# MySensors_AirQuality_Board_2017-11-21_i2.net
KiCad netlist of a schematic drawn in EAGLE
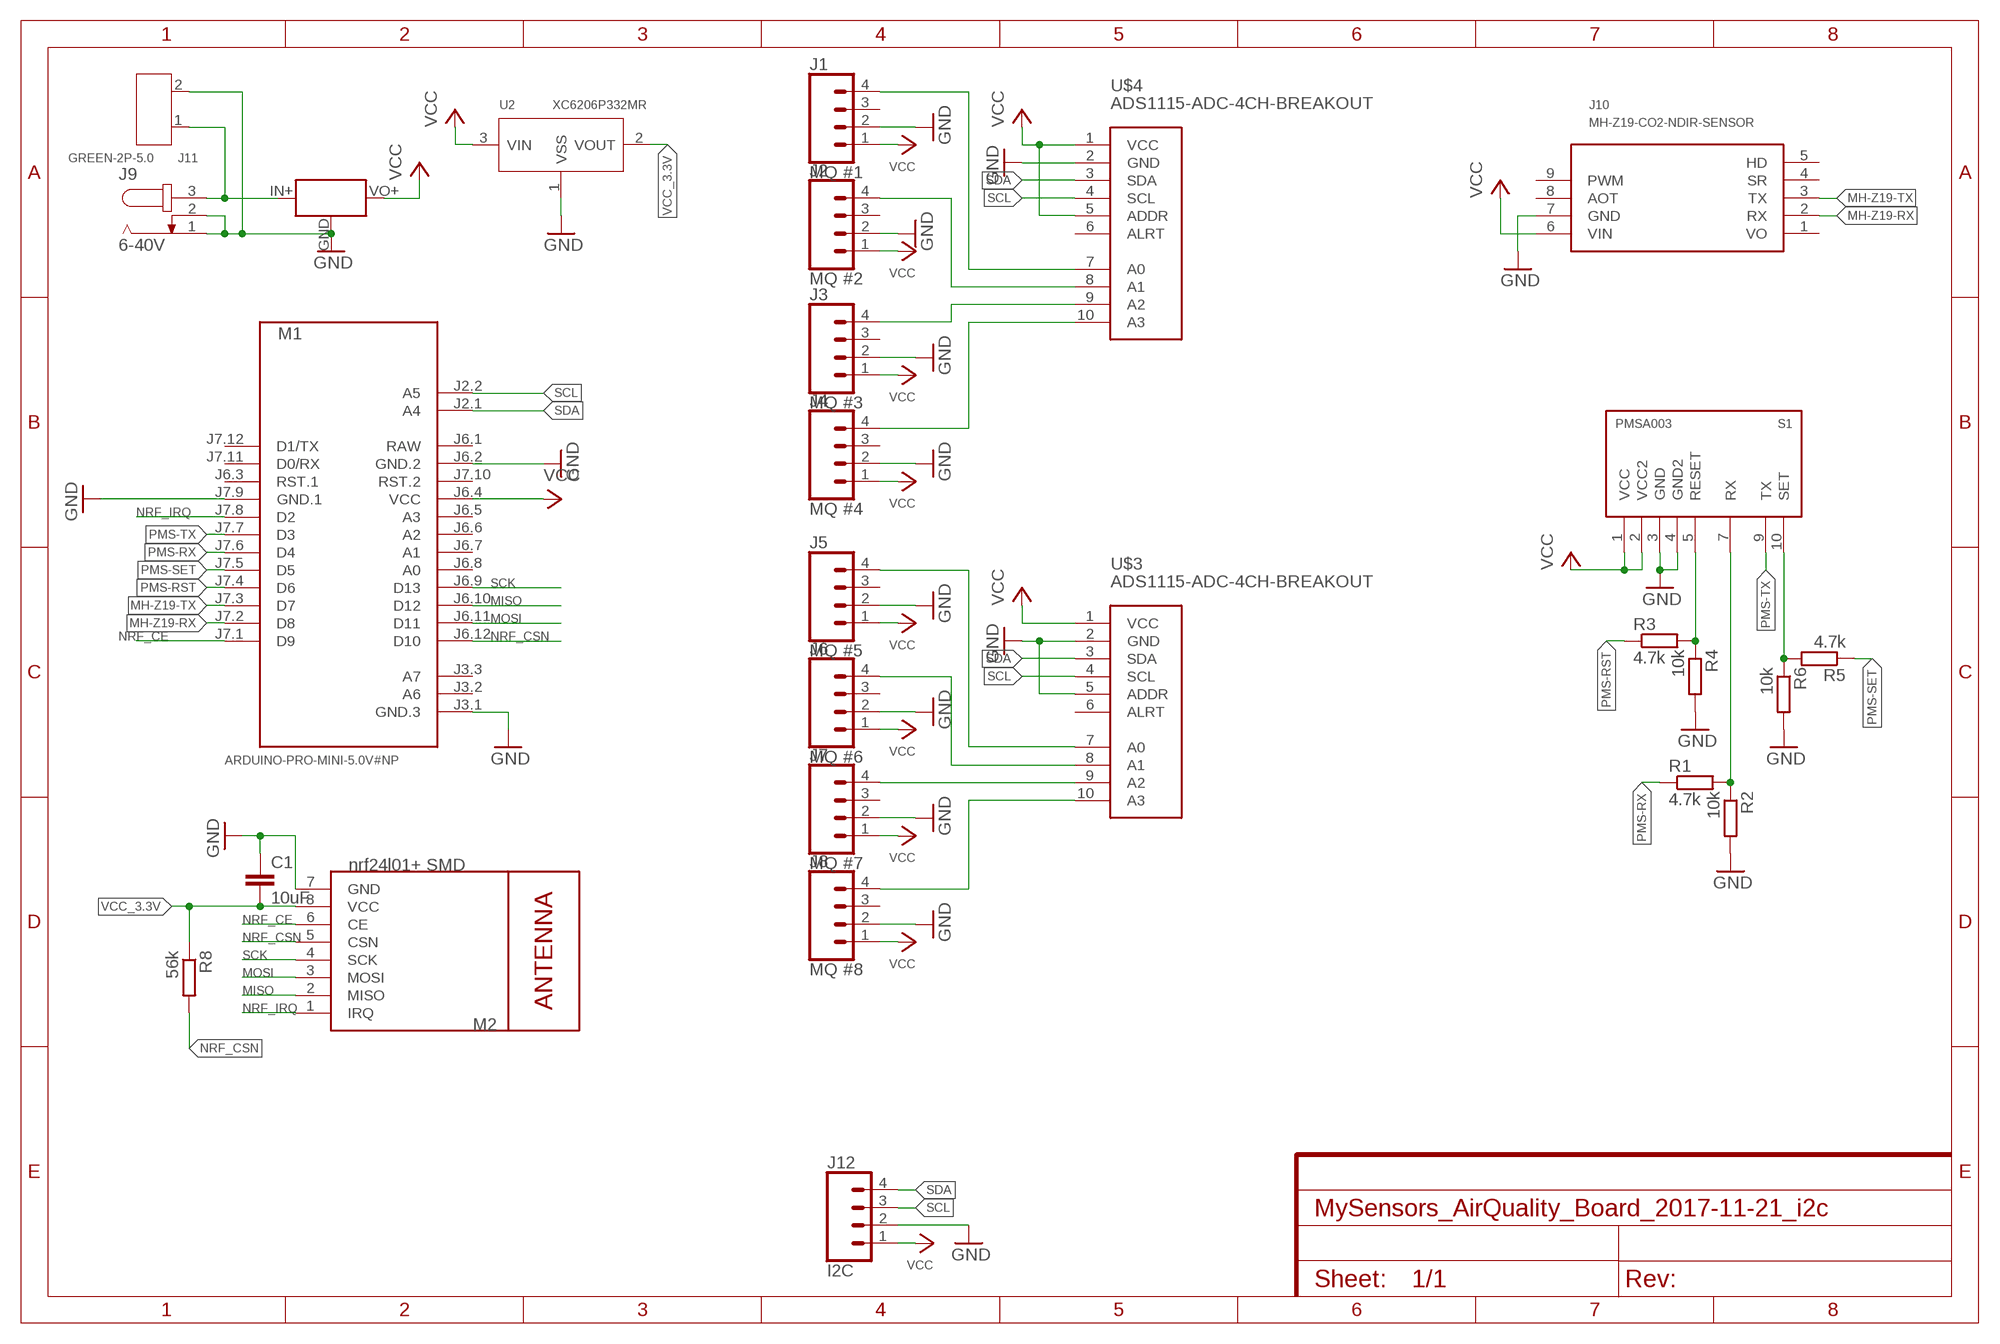
[diagram p0: schematic, sheet 1]

(export (version "E")
  (design (tool "Eeschema 10.0.6"))
  (components
    (comp (ref "C1")
      (value "10uF")
      (footprint "eagle-import:C0805")
      (libsource (lib "eagle-import") (part "C-EUC0805"))
    )
    (comp (ref "J1")
      (value "MQ #1")
      (footprint "eagle-import:1X04")
      (libsource (lib "eagle-import") (part "CONN_04"))
    )
    (comp (ref "J2")
      (value "MQ #2")
      (footprint "eagle-import:1X04")
      (libsource (lib "eagle-import") (part "CONN_04"))
    )
    (comp (ref "J3")
      (value "MQ #3")
      (footprint "eagle-import:1X04")
      (libsource (lib "eagle-import") (part "CONN_04"))
    )
    (comp (ref "J4")
      (value "MQ #4")
      (footprint "eagle-import:1X04")
      (libsource (lib "eagle-import") (part "CONN_04"))
    )
    (comp (ref "J5")
      (value "MQ #5")
      (footprint "eagle-import:1X04")
      (libsource (lib "eagle-import") (part "CONN_04"))
    )
    (comp (ref "J6")
      (value "MQ #6")
      (footprint "eagle-import:1X04")
      (libsource (lib "eagle-import") (part "CONN_04"))
    )
    (comp (ref "J7")
      (value "MQ #7")
      (footprint "eagle-import:1X04")
      (libsource (lib "eagle-import") (part "CONN_04"))
    )
    (comp (ref "J8")
      (value "MQ #8")
      (footprint "eagle-import:1X04")
      (libsource (lib "eagle-import") (part "CONN_04"))
    )
    (comp (ref "J9")
      (value "6-40V")
      (footprint "eagle-import:SPC4078")
      (libsource (lib "eagle-import") (part "JACK-PLUG1"))
    )
    (comp (ref "J10")
      (value "MH-Z19-CO2-NDIR-SENSOR")
      (footprint "eagle-import:MH-Z19")
      (libsource (lib "eagle-import") (part "MH-Z19-CO2-NDIR-SENSOR"))
    )
    (comp (ref "J11")
      (value "GREEN-2P-5.0")
      (footprint "eagle-import:H2-5.0-10.5X8.0MM")
      (libsource (lib "eagle-import") (part "SCREW-TERMINAL-GREEN(2P-5.0)"))
    )
    (comp (ref "J12")
      (value "I2C")
      (footprint "eagle-import:1X04")
      (libsource (lib "eagle-import") (part "CONN_04"))
    )
    (comp (ref "M1")
      (value "ARDUINO-PRO-MINI-5.0V#NP")
      (footprint "eagle-import:ARDUINO-PRO-MINI#NP")
      (libsource (lib "eagle-import") (part "ARDUINO-PRO-MINI-#NP5.0V"))
    )
    (comp (ref "M2")
      (value "nrf24l01+ SMD")
      (footprint "eagle-import:WIRELESS-NRF24L01-SMD")
      (libsource (lib "eagle-import") (part "WIRELESS-NRF24L01SMD"))
    )
    (comp (ref "R1")
      (value "4.7k")
      (footprint "eagle-import:R0805")
      (libsource (lib "eagle-import") (part "resistor_348_R-EU_R0805"))
    )
    (comp (ref "R2")
      (value "10k")
      (footprint "eagle-import:R0805")
      (libsource (lib "eagle-import") (part "resistor_348_R-EU_R0805"))
    )
    (comp (ref "R3")
      (value "4.7k")
      (footprint "eagle-import:R0805")
      (libsource (lib "eagle-import") (part "resistor_348_R-EU_R0805"))
    )
    (comp (ref "R4")
      (value "10k")
      (footprint "eagle-import:R0805")
      (libsource (lib "eagle-import") (part "resistor_348_R-EU_R0805"))
    )
    (comp (ref "R5")
      (value "4.7k")
      (footprint "eagle-import:R0805")
      (libsource (lib "eagle-import") (part "resistor_348_R-EU_R0805"))
    )
    (comp (ref "R6")
      (value "10k")
      (footprint "eagle-import:R0805")
      (libsource (lib "eagle-import") (part "resistor_348_R-EU_R0805"))
    )
    (comp (ref "R8")
      (value "56k")
      (footprint "eagle-import:R0805")
      (libsource (lib "eagle-import") (part "R-EU_R0805"))
    )
    (comp (ref "S1")
      (value "PMSA003")
      (footprint "eagle-import:PMSA003")
      (libsource (lib "eagle-import") (part "PMSA003"))
    )
    (comp (ref "U$2")
      (value "MINI_BUCK_CONVERTER")
      (footprint "eagle-import:MINI_BUCK_CONVERTER")
      (libsource (lib "eagle-import") (part "MINI_BUCK_CONVERTER"))
    )
    (comp (ref "U$3")
      (value "ADS1115-ADC-4CH-BREAKOUT")
      (footprint "eagle-import:ADS1115-ADC-4CH-BREAKOUT")
      (libsource (lib "eagle-import") (part "ADS1115-ADC-4CH-BREAKOUT"))
    )
    (comp (ref "U$4")
      (value "ADS1115-ADC-4CH-BREAKOUT")
      (footprint "eagle-import:ADS1115-ADC-4CH-BREAKOUT")
      (libsource (lib "eagle-import") (part "ADS1115-ADC-4CH-BREAKOUT"))
    )
    (comp (ref "U2")
      (value "XC6206P332MR")
      (footprint "eagle-import:SOT-23")
      (fields (field (name "MPN") "XC6206P332MR-G"))
      (libsource (lib "eagle-import") (part "PMIC-LDO-XC6206P332MR-G(SOT23)"))
    )
  )
  (nets
    (net (code "1") (name "/MISO") (class "Default")
      (node (ref "M1") (pin "J6.10") (pinfunction "D12_J6.10") (pintype "bidirectional"))
      (node (ref "M2") (pin "2") (pinfunction "MISO_2") (pintype "bidirectional"))
    )
    (net (code "2") (name "/MOSI") (class "Default")
      (node (ref "M1") (pin "J6.11") (pinfunction "D11_J6.11") (pintype "bidirectional"))
      (node (ref "M2") (pin "3") (pinfunction "MOSI_3") (pintype "bidirectional"))
    )
    (net (code "3") (name "/NRF_CE") (class "Default")
      (node (ref "M1") (pin "J7.1") (pinfunction "D9_J7.1") (pintype "bidirectional"))
      (node (ref "M2") (pin "6") (pinfunction "CE_6") (pintype "bidirectional"))
    )
    (net (code "4") (name "/NRF_IRQ") (class "Default")
      (node (ref "M1") (pin "J7.8") (pinfunction "D2_J7.8") (pintype "bidirectional"))
      (node (ref "M2") (pin "1") (pinfunction "IRQ_1") (pintype "bidirectional"))
    )
    (net (code "5") (name "/RAW") (class "Default")
      (node (ref "M1") (pin "J6.1") (pinfunction "RAW_J6.1") (pintype "power_in"))
    )
    (net (code "6") (name "/SCK") (class "Default")
      (node (ref "M1") (pin "J6.9") (pinfunction "D13_J6.9") (pintype "bidirectional"))
      (node (ref "M2") (pin "4") (pinfunction "SCK_4") (pintype "bidirectional"))
    )
    (net (code "7") (name "/VO") (class "Default")
      (node (ref "J10") (pin "1") (pinfunction "VO_1") (pintype "power_in"))
    )
    (net (code "8") (name "GND") (class "Default")
      (node (ref "C1") (pin "1") (pinfunction "1_1") (pintype "passive"))
      (node (ref "J1") (pin "2") (pinfunction "2_2") (pintype "passive"))
      (node (ref "J10") (pin "7") (pinfunction "GND_7") (pintype "power_in"))
      (node (ref "J11") (pin "2") (pinfunction "2_2") (pintype "bidirectional"))
      (node (ref "J12") (pin "2") (pinfunction "2_2") (pintype "passive"))
      (node (ref "J2") (pin "2") (pinfunction "2_2") (pintype "passive"))
      (node (ref "J3") (pin "2") (pinfunction "2_2") (pintype "passive"))
      (node (ref "J4") (pin "2") (pinfunction "2_2") (pintype "passive"))
      (node (ref "J5") (pin "2") (pinfunction "2_2") (pintype "passive"))
      (node (ref "J6") (pin "2") (pinfunction "2_2") (pintype "passive"))
      (node (ref "J7") (pin "2") (pinfunction "2_2") (pintype "passive"))
      (node (ref "J8") (pin "2") (pinfunction "2_2") (pintype "passive"))
      (node (ref "J9") (pin "1") (pinfunction "1_1") (pintype "passive"))
      (node (ref "J9") (pin "2") (pinfunction "2_2") (pintype "passive"))
      (node (ref "M1") (pin "J3.1") (pinfunction "GND.3_J3.1") (pintype "bidirectional"))
      (node (ref "M1") (pin "J6.2") (pinfunction "GND.2_J6.2") (pintype "power_in"))
      (node (ref "M1") (pin "J7.9") (pinfunction "GND.1_J7.9") (pintype "power_in"))
      (node (ref "M2") (pin "7") (pinfunction "GND_7") (pintype "power_in"))
      (node (ref "R2") (pin "2") (pinfunction "2_2") (pintype "passive"))
      (node (ref "R4") (pin "2") (pinfunction "2_2") (pintype "passive"))
      (node (ref "R6") (pin "2") (pinfunction "2_2") (pintype "passive"))
      (node (ref "S1") (pin "3") (pinfunction "GND_3") (pintype "bidirectional"))
      (node (ref "S1") (pin "4") (pinfunction "GND2_4") (pintype "bidirectional"))
      (node (ref "U$2") (pin "GND") (pinfunction "GND_GND") (pintype "bidirectional"))
      (node (ref "U$3") (pin "2") (pinfunction "GND_2") (pintype "power_in"))
      (node (ref "U$3") (pin "5") (pinfunction "ADDR_5") (pintype "bidirectional"))
      (node (ref "U$4") (pin "2") (pinfunction "GND_2") (pintype "power_in"))
      (node (ref "U2") (pin "1") (pinfunction "VSS_1") (pintype "power_in"))
    )
    (net (code "9") (name "MH-Z19-RX") (class "Default")
      (node (ref "J10") (pin "2") (pinfunction "RX_2") (pintype "input"))
      (node (ref "M1") (pin "J7.2") (pinfunction "D8_J7.2") (pintype "bidirectional"))
    )
    (net (code "10") (name "MH-Z19-TX") (class "Default")
      (node (ref "J10") (pin "3") (pinfunction "TX_3") (pintype "output"))
      (node (ref "M1") (pin "J7.3") (pinfunction "D7_J7.3") (pintype "bidirectional"))
    )
    (net (code "11") (name "NRF_CSN") (class "Default")
      (node (ref "M1") (pin "J6.12") (pinfunction "D10_J6.12") (pintype "bidirectional"))
      (node (ref "M2") (pin "5") (pinfunction "CSN_5") (pintype "bidirectional"))
      (node (ref "R8") (pin "2") (pinfunction "2_2") (pintype "passive"))
    )
    (net (code "12") (name "Net-(S1-RESET)") (class "Default")
      (node (ref "R3") (pin "2") (pinfunction "2_2") (pintype "passive"))
      (node (ref "R4") (pin "1") (pinfunction "1_1") (pintype "passive"))
      (node (ref "S1") (pin "5") (pinfunction "RESET_5") (pintype "bidirectional"))
    )
    (net (code "13") (name "Net-(S1-RX)") (class "Default")
      (node (ref "R1") (pin "2") (pinfunction "2_2") (pintype "passive"))
      (node (ref "R2") (pin "1") (pinfunction "1_1") (pintype "passive"))
      (node (ref "S1") (pin "7") (pinfunction "RX_7") (pintype "bidirectional"))
    )
    (net (code "14") (name "Net-(S1-SET)") (class "Default")
      (node (ref "R5") (pin "2") (pinfunction "2_2") (pintype "passive"))
      (node (ref "R6") (pin "1") (pinfunction "1_1") (pintype "passive"))
      (node (ref "S1") (pin "10") (pinfunction "SET_10") (pintype "bidirectional"))
    )
    (net (code "15") (name "Net-(U$2-VIN)") (class "Default")
      (node (ref "J11") (pin "1") (pinfunction "1_1") (pintype "bidirectional"))
      (node (ref "J9") (pin "3") (pinfunction "3_3") (pintype "passive"))
      (node (ref "U$2") (pin "IN+") (pinfunction "VIN_IN+") (pintype "input"))
    )
    (net (code "16") (name "Net-(U$3-A0)") (class "Default")
      (node (ref "J5") (pin "4") (pinfunction "4_4") (pintype "passive"))
      (node (ref "U$3") (pin "7") (pinfunction "A0_7") (pintype "input"))
    )
    (net (code "17") (name "Net-(U$3-A1)") (class "Default")
      (node (ref "J6") (pin "4") (pinfunction "4_4") (pintype "passive"))
      (node (ref "U$3") (pin "8") (pinfunction "A1_8") (pintype "input"))
    )
    (net (code "18") (name "Net-(U$3-A2)") (class "Default")
      (node (ref "J7") (pin "4") (pinfunction "4_4") (pintype "passive"))
      (node (ref "U$3") (pin "9") (pinfunction "A2_9") (pintype "input"))
    )
    (net (code "19") (name "Net-(U$3-A3)") (class "Default")
      (node (ref "J8") (pin "4") (pinfunction "4_4") (pintype "passive"))
      (node (ref "U$3") (pin "10") (pinfunction "A3_10") (pintype "input"))
    )
    (net (code "20") (name "Net-(U$4-A0)") (class "Default")
      (node (ref "J1") (pin "4") (pinfunction "4_4") (pintype "passive"))
      (node (ref "U$4") (pin "7") (pinfunction "A0_7") (pintype "input"))
    )
    (net (code "21") (name "Net-(U$4-A1)") (class "Default")
      (node (ref "J2") (pin "4") (pinfunction "4_4") (pintype "passive"))
      (node (ref "U$4") (pin "8") (pinfunction "A1_8") (pintype "input"))
    )
    (net (code "22") (name "Net-(U$4-A2)") (class "Default")
      (node (ref "J3") (pin "4") (pinfunction "4_4") (pintype "passive"))
      (node (ref "U$4") (pin "9") (pinfunction "A2_9") (pintype "input"))
    )
    (net (code "23") (name "Net-(U$4-A3)") (class "Default")
      (node (ref "J4") (pin "4") (pinfunction "4_4") (pintype "passive"))
      (node (ref "U$4") (pin "10") (pinfunction "A3_10") (pintype "input"))
    )
    (net (code "24") (name "PMS-RST") (class "Default")
      (node (ref "M1") (pin "J7.4") (pinfunction "D6_J7.4") (pintype "bidirectional"))
      (node (ref "R3") (pin "1") (pinfunction "1_1") (pintype "passive"))
    )
    (net (code "25") (name "PMS-RX") (class "Default")
      (node (ref "M1") (pin "J7.6") (pinfunction "D4_J7.6") (pintype "bidirectional"))
      (node (ref "R1") (pin "1") (pinfunction "1_1") (pintype "passive"))
    )
    (net (code "26") (name "PMS-SET") (class "Default")
      (node (ref "M1") (pin "J7.5") (pinfunction "D5_J7.5") (pintype "bidirectional"))
      (node (ref "R5") (pin "1") (pinfunction "1_1") (pintype "passive"))
    )
    (net (code "27") (name "PMS-TX") (class "Default")
      (node (ref "M1") (pin "J7.7") (pinfunction "D3_J7.7") (pintype "bidirectional"))
      (node (ref "S1") (pin "9") (pinfunction "TX_9") (pintype "bidirectional"))
    )
    (net (code "28") (name "SCL") (class "Default")
      (node (ref "J12") (pin "3") (pinfunction "3_3") (pintype "passive"))
      (node (ref "M1") (pin "J2.2") (pinfunction "A5_J2.2") (pintype "bidirectional"))
      (node (ref "U$3") (pin "4") (pinfunction "SCL_4") (pintype "bidirectional"))
      (node (ref "U$4") (pin "4") (pinfunction "SCL_4") (pintype "bidirectional"))
    )
    (net (code "29") (name "SDA") (class "Default")
      (node (ref "J12") (pin "4") (pinfunction "4_4") (pintype "passive"))
      (node (ref "M1") (pin "J2.1") (pinfunction "A4_J2.1") (pintype "bidirectional"))
      (node (ref "U$3") (pin "3") (pinfunction "SDA_3") (pintype "bidirectional"))
      (node (ref "U$4") (pin "3") (pinfunction "SDA_3") (pintype "bidirectional"))
    )
    (net (code "30") (name "VCC") (class "Default")
      (node (ref "J1") (pin "1") (pinfunction "1_1") (pintype "passive"))
      (node (ref "J10") (pin "6") (pinfunction "VIN_6") (pintype "power_in"))
      (node (ref "J12") (pin "1") (pinfunction "1_1") (pintype "passive"))
      (node (ref "J2") (pin "1") (pinfunction "1_1") (pintype "passive"))
      (node (ref "J3") (pin "1") (pinfunction "1_1") (pintype "passive"))
      (node (ref "J4") (pin "1") (pinfunction "1_1") (pintype "passive"))
      (node (ref "J5") (pin "1") (pinfunction "1_1") (pintype "passive"))
      (node (ref "J6") (pin "1") (pinfunction "1_1") (pintype "passive"))
      (node (ref "J7") (pin "1") (pinfunction "1_1") (pintype "passive"))
      (node (ref "J8") (pin "1") (pinfunction "1_1") (pintype "passive"))
      (node (ref "M1") (pin "J6.4") (pinfunction "VCC_J6.4") (pintype "power_in"))
      (node (ref "S1") (pin "1") (pinfunction "VCC_1") (pintype "bidirectional"))
      (node (ref "S1") (pin "2") (pinfunction "VCC2_2") (pintype "bidirectional"))
      (node (ref "U$2") (pin "VO+") (pinfunction "VOUT_VO+") (pintype "power_in"))
      (node (ref "U$3") (pin "1") (pinfunction "VCC_1") (pintype "power_in"))
      (node (ref "U$4") (pin "1") (pinfunction "VCC_1") (pintype "power_in"))
      (node (ref "U$4") (pin "5") (pinfunction "ADDR_5") (pintype "bidirectional"))
      (node (ref "U2") (pin "3") (pinfunction "VIN_3") (pintype "input"))
    )
    (net (code "31") (name "VCC_3.3V") (class "Default")
      (node (ref "C1") (pin "2") (pinfunction "2_2") (pintype "passive"))
      (node (ref "M2") (pin "8") (pinfunction "VCC_8") (pintype "power_in"))
      (node (ref "R8") (pin "1") (pinfunction "1_1") (pintype "passive"))
      (node (ref "U2") (pin "2") (pinfunction "VOUT_2") (pintype "output"))
    )
    (net (code "32") (name "unconnected-(J1-Pad3)") (class "Default")
      (node (ref "J1") (pin "3") (pinfunction "3_3") (pintype "passive"))
    )
    (net (code "33") (name "unconnected-(J2-Pad3)") (class "Default")
      (node (ref "J2") (pin "3") (pinfunction "3_3") (pintype "passive"))
    )
    (net (code "34") (name "unconnected-(J3-Pad3)") (class "Default")
      (node (ref "J3") (pin "3") (pinfunction "3_3") (pintype "passive"))
    )
    (net (code "35") (name "unconnected-(J4-Pad3)") (class "Default")
      (node (ref "J4") (pin "3") (pinfunction "3_3") (pintype "passive"))
    )
    (net (code "36") (name "unconnected-(J5-Pad3)") (class "Default")
      (node (ref "J5") (pin "3") (pinfunction "3_3") (pintype "passive"))
    )
    (net (code "37") (name "unconnected-(J6-Pad3)") (class "Default")
      (node (ref "J6") (pin "3") (pinfunction "3_3") (pintype "passive"))
    )
    (net (code "38") (name "unconnected-(J7-Pad3)") (class "Default")
      (node (ref "J7") (pin "3") (pinfunction "3_3") (pintype "passive"))
    )
    (net (code "39") (name "unconnected-(J8-Pad3)") (class "Default")
      (node (ref "J8") (pin "3") (pinfunction "3_3") (pintype "passive"))
    )
    (net (code "40") (name "unconnected-(J10-AOT-Pad8)") (class "Default")
      (node (ref "J10") (pin "8") (pinfunction "AOT_8") (pintype "no_connect"))
    )
    (net (code "41") (name "unconnected-(J10-HD-Pad5)") (class "Default")
      (node (ref "J10") (pin "5") (pinfunction "HD_5") (pintype "input"))
    )
    (net (code "42") (name "unconnected-(J10-PWM-Pad9)") (class "Default")
      (node (ref "J10") (pin "9") (pinfunction "PWM_9") (pintype "output"))
    )
    (net (code "43") (name "unconnected-(J10-SR-Pad4)") (class "Default")
      (node (ref "J10") (pin "4") (pinfunction "SR_4") (pintype "no_connect"))
    )
    (net (code "44") (name "unconnected-(M1-A0-PadJ6.8)") (class "Default")
      (node (ref "M1") (pin "J6.8") (pinfunction "A0_J6.8") (pintype "bidirectional"))
    )
    (net (code "45") (name "unconnected-(M1-A1-PadJ6.7)") (class "Default")
      (node (ref "M1") (pin "J6.7") (pinfunction "A1_J6.7") (pintype "bidirectional"))
    )
    (net (code "46") (name "unconnected-(M1-A2-PadJ6.6)") (class "Default")
      (node (ref "M1") (pin "J6.6") (pinfunction "A2_J6.6") (pintype "bidirectional"))
    )
    (net (code "47") (name "unconnected-(M1-A3-PadJ6.5)") (class "Default")
      (node (ref "M1") (pin "J6.5") (pinfunction "A3_J6.5") (pintype "bidirectional"))
    )
    (net (code "48") (name "unconnected-(M1-A6-PadJ3.2)") (class "Default")
      (node (ref "M1") (pin "J3.2") (pinfunction "A6_J3.2") (pintype "bidirectional"))
    )
    (net (code "49") (name "unconnected-(M1-A7-PadJ3.3)") (class "Default")
      (node (ref "M1") (pin "J3.3") (pinfunction "A7_J3.3") (pintype "bidirectional"))
    )
    (net (code "50") (name "unconnected-(M1-D0{slash}RX-PadJ7.11)") (class "Default")
      (node (ref "M1") (pin "J7.11") (pinfunction "D0/RX_J7.11") (pintype "bidirectional"))
    )
    (net (code "51") (name "unconnected-(M1-D1{slash}TX-PadJ7.12)") (class "Default")
      (node (ref "M1") (pin "J7.12") (pinfunction "D1/TX_J7.12") (pintype "bidirectional"))
    )
    (net (code "52") (name "unconnected-(M1-RST.1-PadJ6.3)") (class "Default")
      (node (ref "M1") (pin "J6.3") (pinfunction "RST.1_J6.3") (pintype "bidirectional"))
    )
    (net (code "53") (name "unconnected-(M1-RST.2-PadJ7.10)") (class "Default")
      (node (ref "M1") (pin "J7.10") (pinfunction "RST.2_J7.10") (pintype "bidirectional"))
    )
    (net (code "54") (name "unconnected-(U$3-ALRT-Pad6)") (class "Default")
      (node (ref "U$3") (pin "6") (pinfunction "ALRT_6") (pintype "bidirectional"))
    )
    (net (code "55") (name "unconnected-(U$4-ALRT-Pad6)") (class "Default")
      (node (ref "U$4") (pin "6") (pinfunction "ALRT_6") (pintype "bidirectional"))
    )
  )
)
